# Controle_Motor.net
KiCad netlist of a schematic drawn in Altium Designer
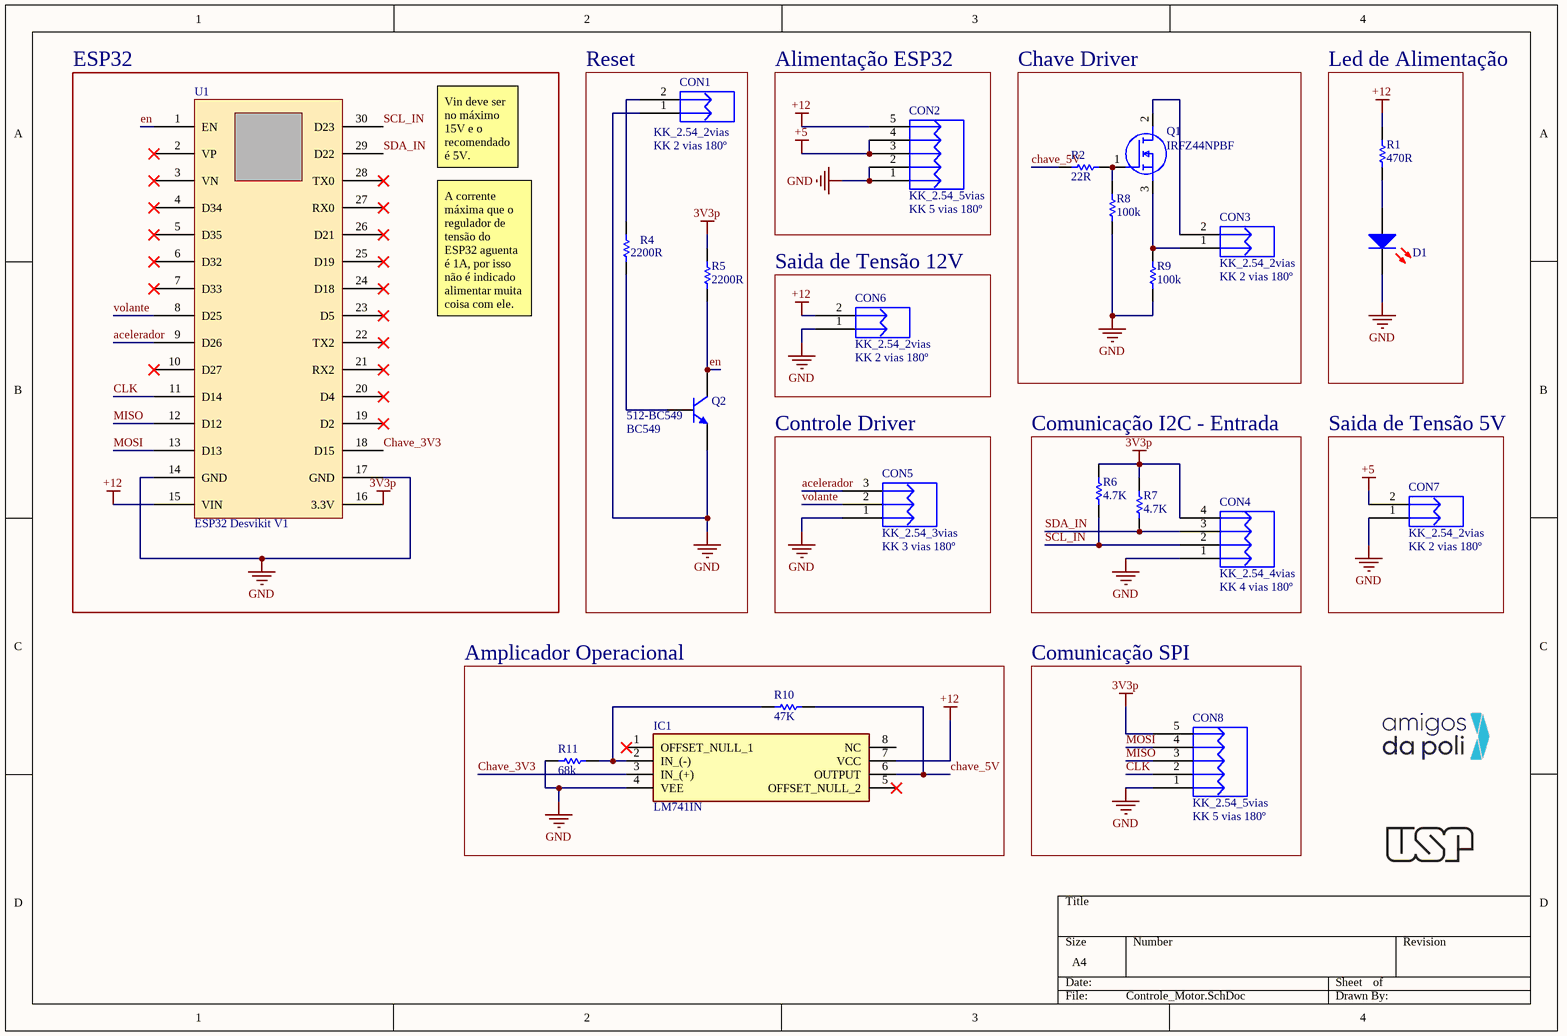
[diagram p0: Controle_Motor.SchDoc]

(export (version "E")
  (design (tool "Eeschema 10.0.6"))
  (components
    (comp (ref "CON1")
      (value "KK_2.54_2vias")
      (footprint "KK_2VIAS_180º")
      (description "Conector KK 2.54mm 2 vias")
      (fields (field (name "VALOR") "KK 2 vias 180º"))
      (libsource (lib "Conectores_Sch") (part "KK_2.54_2vias"))
    )
    (comp (ref "CON2")
      (value "KK_2.54_5vias")
      (footprint "KK_5vias_180°")
      (description "Conector KK 2.54mm 5 vias")
      (fields (field (name "VALOR") "KK 5 vias 180º"))
      (libsource (lib "Conectores_Sch") (part "KK_2.54_5vias"))
    )
    (comp (ref "CON3")
      (value "KK_2.54_2vias")
      (footprint "KK_2VIAS_180º")
      (description "Conector KK 2.54mm 2 vias")
      (fields (field (name "VALOR") "KK 2 vias 180º"))
      (libsource (lib "Conectores_Sch") (part "KK_2.54_2vias"))
    )
    (comp (ref "CON4")
      (value "KK_2.54_4vias")
      (footprint "KK_4vias_180°")
      (description "Conector KK 2.54mm 4 vias")
      (fields (field (name "VALOR") "KK 4 vias 180º"))
      (libsource (lib "Conectores_Sch") (part "KK_2.54_4vias"))
    )
    (comp (ref "CON5")
      (value "KK_2.54_3vias")
      (footprint "KK_3vias_180º")
      (description "Conector KK 2.54mm 3 vias")
      (fields (field (name "VALOR") "KK 3 vias 180º"))
      (libsource (lib "Conectores_Sch") (part "KK_2.54_3vias"))
    )
    (comp (ref "CON6")
      (value "KK_2.54_2vias")
      (footprint "KK_2VIAS_180º")
      (description "Conector KK 2.54mm 2 vias")
      (fields (field (name "VALOR") "KK 2 vias 180º"))
      (libsource (lib "Conectores_Sch") (part "KK_2.54_2vias"))
    )
    (comp (ref "CON7")
      (value "KK_2.54_2vias")
      (footprint "KK_2VIAS_180º")
      (description "Conector KK 2.54mm 2 vias")
      (fields (field (name "VALOR") "KK 2 vias 180º"))
      (libsource (lib "Conectores_Sch") (part "KK_2.54_2vias"))
    )
    (comp (ref "CON8")
      (value "KK_2.54_5vias")
      (footprint "KK_5vias_180°")
      (description "Conector KK 2.54mm 5 vias")
      (fields (field (name "VALOR") "KK 5 vias 180º"))
      (libsource (lib "Conectores_Sch") (part "KK_2.54_5vias"))
    )
    (comp (ref "D1")
      (value "LED 5MM RED")
      (footprint "LED 5MM RED")
      (fields (field (name "MANUFACTURER") "Paralight") (field (name "MANUFACTURER PART NUMBER") "IMP585"))
      (libsource (lib "esp32") (part "LED 5MM RED"))
    )
    (comp (ref "IC1")
      (value "LM741IN")
      (footprint "SamacSys:DIP762W56P254L920H508Q8N")
      (description "Integrated Circuit")
      (fields (field (name "MOUSER PART NUMBER") "512-LM741IN"))
      (libsource (lib "*") (part "LM741IN"))
    )
    (comp (ref "Q1")
      (value "IRFZ44NPBF")
      (footprint "SamacSys:TO254P483X1016X1994-3P")
      (description "MOSFET (N-Channel)")
      (fields (field (name "MOUSER PART NUMBER") "942-IRFZ44NPBF"))
      (libsource (lib "*") (part "IRFZ44NPBF"))
    )
    (comp (ref "Q2")
      (value "BC549")
      (footprint "TO92")
      (description "TRANS NPN 30V 0.1A TO-92")
      (fields
        (field (name "MANUFACTURER") "Fairchild Semiconductor")
        (field (name "SUPPLIER PART NUMBER 1") "512-BC549")
      )
      (libsource (lib "PS_Balanca") (part "BC549"))
    )
    (comp (ref "R1")
      (value "RES 470R 1/4W CARBON FILM")
      (footprint "RES 470R 1/4W CARBON FILM")
      (description "RES 470R OHM 1/4W 5% CARBON FILM")
      (fields
        (field (name "MANUFACTURER") "Ty-Ohm")
        (field (name "MANUFACTURER PART NUMBER") "CR25")
        (field (name "RESISTANCE (OHMS)") "470R")
      )
      (libsource (lib "esp32") (part "RES 470R 1/4W CARBON FILM"))
    )
    (comp (ref "R2")
      (value "RES 470R 1/4W CARBON FILM")
      (footprint "RES 470R 1/4W CARBON FILM")
      (description "RES 470R OHM 1/4W 5% CARBON FILM")
      (fields
        (field (name "MANUFACTURER") "Ty-Ohm")
        (field (name "MANUFACTURER PART NUMBER") "CR25")
        (field (name "RESISTANCE (OHMS)") "22R")
      )
      (libsource (lib "esp32") (part "RES 470R 1/4W CARBON FILM"))
    )
    (comp (ref "R4")
      (value "RES 470R 1/4W CARBON FILM")
      (footprint "RES 470R 1/4W CARBON FILM")
      (description "RES 470R OHM 1/4W 5% CARBON FILM")
      (fields
        (field (name "MANUFACTURER") "Ty-Ohm")
        (field (name "MANUFACTURER PART NUMBER") "CR25")
        (field (name "RESISTANCE (OHMS)") "2200R")
      )
      (libsource (lib "esp32") (part "RES 470R 1/4W CARBON FILM"))
    )
    (comp (ref "R5")
      (value "RES 470R 1/4W CARBON FILM")
      (footprint "RES 470R 1/4W CARBON FILM")
      (description "RES 470R OHM 1/4W 5% CARBON FILM")
      (fields
        (field (name "MANUFACTURER") "Ty-Ohm")
        (field (name "MANUFACTURER PART NUMBER") "CR25")
        (field (name "RESISTANCE (OHMS)") "2200R")
      )
      (libsource (lib "esp32") (part "RES 470R 1/4W CARBON FILM"))
    )
    (comp (ref "R6")
      (value "4.7K")
      (footprint "RES 4.7K 1/4W CARBON FILM")
      (description "RES 4.7K OHM 1/4W 5% CARBON FILM")
      (fields (field (name "MANUFACTURER") "Ty-Ohm") (field (name "MANUFACTURER PART NUMBER") "CR25"))
      (libsource (lib "esp32") (part "RES 4.7K 1/4W CARBON FILM"))
    )
    (comp (ref "R7")
      (value "4.7K")
      (footprint "RES 4.7K 1/4W CARBON FILM")
      (description "RES 4.7K OHM 1/4W 5% CARBON FILM")
      (fields (field (name "MANUFACTURER") "Ty-Ohm") (field (name "MANUFACTURER PART NUMBER") "CR25"))
      (libsource (lib "esp32") (part "RES 4.7K 1/4W CARBON FILM"))
    )
    (comp (ref "R8")
      (value "RES 470R 1/4W CARBON FILM")
      (footprint "RES 470R 1/4W CARBON FILM")
      (description "RES 470R OHM 1/4W 5% CARBON FILM")
      (fields
        (field (name "MANUFACTURER") "Ty-Ohm")
        (field (name "MANUFACTURER PART NUMBER") "CR25")
        (field (name "RESISTANCE (OHMS)") "100k")
      )
      (libsource (lib "esp32") (part "RES 470R 1/4W CARBON FILM"))
    )
    (comp (ref "R9")
      (value "RES 470R 1/4W CARBON FILM")
      (footprint "RES 470R 1/4W CARBON FILM")
      (description "RES 470R OHM 1/4W 5% CARBON FILM")
      (fields
        (field (name "MANUFACTURER") "Ty-Ohm")
        (field (name "MANUFACTURER PART NUMBER") "CR25")
        (field (name "RESISTANCE (OHMS)") "100k")
      )
      (libsource (lib "esp32") (part "RES 470R 1/4W CARBON FILM"))
    )
    (comp (ref "R10")
      (value "47K")
      (footprint "RES 4.7K 1/4W CARBON FILM")
      (description "RES 4.7K OHM 1/4W 5% CARBON FILM")
      (fields (field (name "MANUFACTURER") "Ty-Ohm") (field (name "MANUFACTURER PART NUMBER") "CR25"))
      (libsource (lib "esp32") (part "RES 4.7K 1/4W CARBON FILM"))
    )
    (comp (ref "R11")
      (value "68k")
      (footprint "RES 4.7K 1/4W CARBON FILM")
      (description "RES 4.7K OHM 1/4W 5% CARBON FILM")
      (fields (field (name "MANUFACTURER") "Ty-Ohm") (field (name "MANUFACTURER PART NUMBER") "CR25"))
      (libsource (lib "esp32") (part "RES 4.7K 1/4W CARBON FILM"))
    )
    (comp (ref "U1")
      (value "ESP32 Desvikit V1")
      (footprint "ESP32_Desvikit_v1")
      (description "microcontrolador com moculo bluethoth e wifi")
      (fields (field (name "Comment") "microcontrolador"))
      (libsource (lib "esp32") (part "ESP32 Desvikit v1"))
    )
  )
  (nets
    (net (code "1") (name "+5") (class "Default")
      (node (ref "CON2") (pin "3") (pintype "passive"))
      (node (ref "CON2") (pin "4") (pintype "passive"))
      (node (ref "CON7") (pin "2") (pintype "passive"))
    )
    (net (code "2") (name "+12") (class "Default")
      (node (ref "CON2") (pin "5") (pintype "passive"))
      (node (ref "CON6") (pin "2") (pintype "passive"))
      (node (ref "IC1") (pin "7") (pinfunction "VCC_7") (pintype "passive"))
      (node (ref "R1") (pin "2") (pinfunction "2_2") (pintype "passive"))
      (node (ref "U1") (pin "15") (pinfunction "VIN_15") (pintype "passive"))
    )
    (net (code "3") (name "/CLK") (class "Default")
      (node (ref "CON8") (pin "2") (pintype "passive"))
      (node (ref "U1") (pin "11") (pinfunction "D14_11") (pintype "passive"))
    )
    (net (code "4") (name "/Chave_3V3") (class "Default")
      (node (ref "IC1") (pin "3") (pinfunction "IN_(+)_3") (pintype "passive"))
      (node (ref "U1") (pin "18") (pinfunction "D15_18") (pintype "passive"))
    )
    (net (code "5") (name "/MISO") (class "Default")
      (node (ref "CON8") (pin "3") (pintype "passive"))
      (node (ref "U1") (pin "12") (pinfunction "D12_12") (pintype "passive"))
    )
    (net (code "6") (name "/MOSI") (class "Default")
      (node (ref "CON8") (pin "4") (pintype "passive"))
      (node (ref "U1") (pin "13") (pinfunction "D13_13") (pintype "passive"))
    )
    (net (code "7") (name "/SCL_IN") (class "Default")
      (node (ref "CON4") (pin "2") (pintype "passive"))
      (node (ref "R6") (pin "2") (pinfunction "2_2") (pintype "passive"))
      (node (ref "U1") (pin "30") (pinfunction "D23_30") (pintype "passive"))
    )
    (net (code "8") (name "/SDA_IN") (class "Default")
      (node (ref "CON4") (pin "3") (pintype "passive"))
      (node (ref "R7") (pin "2") (pinfunction "2_2") (pintype "passive"))
      (node (ref "U1") (pin "29") (pinfunction "D22_29") (pintype "passive"))
    )
    (net (code "9") (name "/acelerador") (class "Default")
      (node (ref "CON5") (pin "3") (pintype "passive"))
      (node (ref "U1") (pin "9") (pinfunction "D26_9") (pintype "passive"))
    )
    (net (code "10") (name "/chave_5V") (class "Default")
      (node (ref "IC1") (pin "6") (pinfunction "OUTPUT_6") (pintype "passive"))
      (node (ref "R10") (pin "2") (pinfunction "2_2") (pintype "passive"))
      (node (ref "R2") (pin "2") (pinfunction "2_2") (pintype "passive"))
    )
    (net (code "11") (name "/en") (class "Default")
      (node (ref "Q2") (pin "1") (pinfunction "C_1") (pintype "passive"))
      (node (ref "R5") (pin "1") (pinfunction "1_1") (pintype "passive"))
      (node (ref "U1") (pin "1") (pinfunction "EN_1") (pintype "passive"))
    )
    (net (code "12") (name "/volante") (class "Default")
      (node (ref "CON5") (pin "2") (pintype "passive"))
      (node (ref "U1") (pin "8") (pinfunction "D25_8") (pintype "passive"))
    )
    (net (code "13") (name "3V3p") (class "Default")
      (node (ref "CON4") (pin "4") (pintype "passive"))
      (node (ref "CON8") (pin "5") (pintype "passive"))
      (node (ref "R5") (pin "2") (pinfunction "2_2") (pintype "passive"))
      (node (ref "R6") (pin "1") (pinfunction "1_1") (pintype "passive"))
      (node (ref "R7") (pin "1") (pinfunction "1_1") (pintype "passive"))
      (node (ref "U1") (pin "16") (pinfunction "3.3V_16") (pintype "passive"))
    )
    (net (code "14") (name "GND") (class "Default")
      (node (ref "CON1") (pin "1") (pintype "passive"))
      (node (ref "CON2") (pin "1") (pintype "passive"))
      (node (ref "CON2") (pin "2") (pintype "passive"))
      (node (ref "CON4") (pin "1") (pintype "passive"))
      (node (ref "CON5") (pin "1") (pintype "passive"))
      (node (ref "CON6") (pin "1") (pintype "passive"))
      (node (ref "CON7") (pin "1") (pintype "passive"))
      (node (ref "CON8") (pin "1") (pintype "passive"))
      (node (ref "D1") (pin "2") (pinfunction "K_2") (pintype "passive"))
      (node (ref "IC1") (pin "4") (pinfunction "VEE_4") (pintype "passive"))
      (node (ref "Q2") (pin "3") (pinfunction "E_3") (pintype "passive"))
      (node (ref "R11") (pin "1") (pinfunction "1_1") (pintype "passive"))
      (node (ref "R8") (pin "1") (pinfunction "1_1") (pintype "passive"))
      (node (ref "R9") (pin "1") (pinfunction "1_1") (pintype "passive"))
      (node (ref "U1") (pin "14") (pinfunction "GND_14") (pintype "passive"))
      (node (ref "U1") (pin "17") (pinfunction "GND_17") (pintype "passive"))
    )
    (net (code "15") (name "Net-(CON1-Pad2)") (class "Default")
      (node (ref "CON1") (pin "2") (pintype "passive"))
      (node (ref "R4") (pin "2") (pinfunction "2_2") (pintype "passive"))
    )
    (net (code "16") (name "Net-(D1-A)") (class "Default")
      (node (ref "D1") (pin "1") (pinfunction "A_1") (pintype "passive"))
      (node (ref "R1") (pin "1") (pinfunction "1_1") (pintype "passive"))
    )
    (net (code "17") (name "Net-(IC1-IN_(-))") (class "Default")
      (node (ref "IC1") (pin "2") (pinfunction "IN_(-)_2") (pintype "passive"))
      (node (ref "R10") (pin "1") (pinfunction "1_1") (pintype "passive"))
      (node (ref "R11") (pin "2") (pinfunction "2_2") (pintype "passive"))
    )
    (net (code "18") (name "Net-(Q1-D)") (class "Default")
      (node (ref "CON3") (pin "2") (pintype "passive"))
      (node (ref "Q1") (pin "2") (pinfunction "D_2") (pintype "passive"))
    )
    (net (code "19") (name "Net-(Q1-G)") (class "Default")
      (node (ref "Q1") (pin "1") (pinfunction "G_1") (pintype "passive"))
      (node (ref "R2") (pin "1") (pinfunction "1_1") (pintype "passive"))
      (node (ref "R8") (pin "2") (pinfunction "2_2") (pintype "passive"))
    )
    (net (code "20") (name "Net-(Q1-S)") (class "Default")
      (node (ref "CON3") (pin "1") (pintype "passive"))
      (node (ref "Q1") (pin "3") (pinfunction "S_3") (pintype "passive"))
      (node (ref "R9") (pin "2") (pinfunction "2_2") (pintype "passive"))
    )
    (net (code "21") (name "Net-(Q2-B)") (class "Default")
      (node (ref "Q2") (pin "2") (pinfunction "B_2") (pintype "passive"))
      (node (ref "R4") (pin "1") (pinfunction "1_1") (pintype "passive"))
    )
    (net (code "22") (name "unconnected-(IC1-NC-Pad8)") (class "Default")
      (node (ref "IC1") (pin "8") (pinfunction "NC_8") (pintype "passive"))
    )
    (net (code "23") (name "unconnected-(IC1-OFFSET_NULL_1-Pad1)") (class "Default")
      (node (ref "IC1") (pin "1") (pinfunction "OFFSET_NULL_1_1") (pintype "passive+no_connect"))
    )
    (net (code "24") (name "unconnected-(IC1-OFFSET_NULL_2-Pad5)") (class "Default")
      (node (ref "IC1") (pin "5") (pinfunction "OFFSET_NULL_2_5") (pintype "passive+no_connect"))
    )
    (net (code "25") (name "unconnected-(U1-D2-Pad19)") (class "Default")
      (node (ref "U1") (pin "19") (pinfunction "D2_19") (pintype "passive+no_connect"))
    )
    (net (code "26") (name "unconnected-(U1-D4-Pad20)") (class "Default")
      (node (ref "U1") (pin "20") (pinfunction "D4_20") (pintype "passive+no_connect"))
    )
    (net (code "27") (name "unconnected-(U1-D5-Pad23)") (class "Default")
      (node (ref "U1") (pin "23") (pinfunction "D5_23") (pintype "passive+no_connect"))
    )
    (net (code "28") (name "unconnected-(U1-D18-Pad24)") (class "Default")
      (node (ref "U1") (pin "24") (pinfunction "D18_24") (pintype "passive+no_connect"))
    )
    (net (code "29") (name "unconnected-(U1-D19-Pad25)") (class "Default")
      (node (ref "U1") (pin "25") (pinfunction "D19_25") (pintype "passive+no_connect"))
    )
    (net (code "30") (name "unconnected-(U1-D21-Pad26)") (class "Default")
      (node (ref "U1") (pin "26") (pinfunction "D21_26") (pintype "passive+no_connect"))
    )
    (net (code "31") (name "unconnected-(U1-D27-Pad10)") (class "Default")
      (node (ref "U1") (pin "10") (pinfunction "D27_10") (pintype "passive+no_connect"))
    )
    (net (code "32") (name "unconnected-(U1-D32-Pad6)") (class "Default")
      (node (ref "U1") (pin "6") (pinfunction "D32_6") (pintype "passive+no_connect"))
    )
    (net (code "33") (name "unconnected-(U1-D33-Pad7)") (class "Default")
      (node (ref "U1") (pin "7") (pinfunction "D33_7") (pintype "passive+no_connect"))
    )
    (net (code "34") (name "unconnected-(U1-D34-Pad4)") (class "Default")
      (node (ref "U1") (pin "4") (pinfunction "D34_4") (pintype "passive+no_connect"))
    )
    (net (code "35") (name "unconnected-(U1-D35-Pad5)") (class "Default")
      (node (ref "U1") (pin "5") (pinfunction "D35_5") (pintype "passive+no_connect"))
    )
    (net (code "36") (name "unconnected-(U1-RX0-Pad27)") (class "Default")
      (node (ref "U1") (pin "27") (pinfunction "RX0_27") (pintype "passive+no_connect"))
    )
    (net (code "37") (name "unconnected-(U1-RX2-Pad21)") (class "Default")
      (node (ref "U1") (pin "21") (pinfunction "RX2_21") (pintype "passive+no_connect"))
    )
    (net (code "38") (name "unconnected-(U1-TX0-Pad28)") (class "Default")
      (node (ref "U1") (pin "28") (pinfunction "TX0_28") (pintype "passive+no_connect"))
    )
    (net (code "39") (name "unconnected-(U1-TX2-Pad22)") (class "Default")
      (node (ref "U1") (pin "22") (pinfunction "TX2_22") (pintype "passive+no_connect"))
    )
    (net (code "40") (name "unconnected-(U1-VN-Pad3)") (class "Default")
      (node (ref "U1") (pin "3") (pinfunction "VN_3") (pintype "passive+no_connect"))
    )
    (net (code "41") (name "unconnected-(U1-VP-Pad2)") (class "Default")
      (node (ref "U1") (pin "2") (pinfunction "VP_2") (pintype "passive+no_connect"))
    )
  )
)
